# Ind_board.net
KiCad netlist of a schematic drawn in Altium Designer
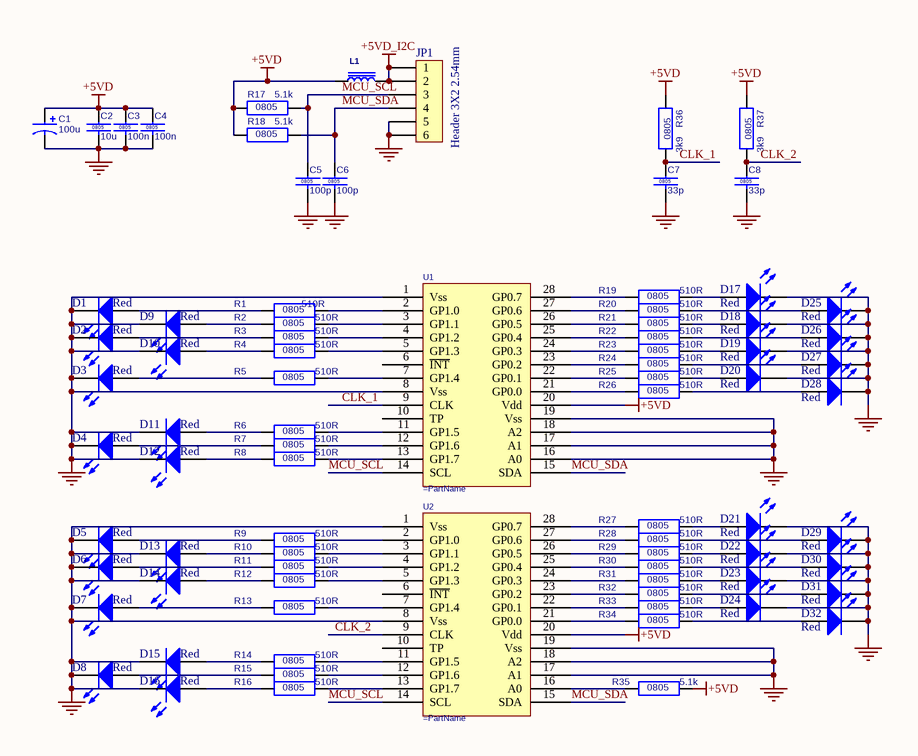
[diagram p0: Ind_board.SchDoc]

(export (version "E")
  (design (tool "Eeschema 10.0.6"))
  (components
    (comp (ref "C1")
      (value "100u")
      (footprint "CEH12.5D10P5.0")
      (description "Electrolytic capacitor")
      (fields
        (field (name "PART NUMBER") "CEH12.5D10P5.0M-50V-100U")
        (field (name "VOLTAGE") "50V")
        (field (name "PUBLISHER") "ppavlov")
      )
      (libsource (lib "Aldiva_Altium_Library") (part "Capacitor_polar"))
    )
    (comp (ref "C2")
      (value "10u")
      (footprint "RC0805")
      (description "Chip capacitor, 20p")
      (fields
        (field (name "VOLTAGE") "16V")
        (field (name "MANUFACTURER") "KEMET, YAGEO")
        (field (name "CASE") "0805")
        (field (name "PUBLISHER") "tkondratyuk")
      )
      (libsource (lib "Aldiva_Altium_Library") (part "Capacitor_nonpolar_case"))
    )
    (comp (ref "C3")
      (value "100n")
      (footprint "RC0805")
      (description "Chip capacitor, 20p")
      (fields
        (field (name "VOLTAGE") "50V")
        (field (name "MANUFACTURER") "KEMET, YAGEO")
        (field (name "CASE") "0805")
        (field (name "PUBLISHER") "ppavlov")
      )
      (libsource (lib "Aldiva_Altium_Library") (part "Capacitor_nonpolar_case"))
    )
    (comp (ref "C4")
      (value "100n")
      (footprint "RC0805")
      (description "Chip capacitor, 20p")
      (fields
        (field (name "VOLTAGE") "50V")
        (field (name "MANUFACTURER") "KEMET, YAGEO")
        (field (name "CASE") "0805")
        (field (name "PUBLISHER") "ppavlov")
      )
      (libsource (lib "Aldiva_Altium_Library") (part "Capacitor_nonpolar_case"))
    )
    (comp (ref "C5")
      (value "100p")
      (footprint "RC0805")
      (description "Chip capacitor, 20p")
      (fields
        (field (name "VOLTAGE") "50V")
        (field (name "MANUFACTURER") "KEMET, YAGEO")
        (field (name "CASE") "0805")
        (field (name "PUBLISHER") "ppavlov")
      )
      (libsource (lib "Aldiva_Altium_Library") (part "Capacitor_nonpolar_case"))
    )
    (comp (ref "C6")
      (value "100p")
      (footprint "RC0805")
      (description "Chip capacitor, 20p")
      (fields
        (field (name "VOLTAGE") "50V")
        (field (name "MANUFACTURER") "KEMET, YAGEO")
        (field (name "CASE") "0805")
        (field (name "PUBLISHER") "ppavlov")
      )
      (libsource (lib "Aldiva_Altium_Library") (part "Capacitor_nonpolar_case"))
    )
    (comp (ref "C7")
      (value "33p")
      (footprint "RC0805")
      (description "Chip capacitor, 20p")
      (fields
        (field (name "VOLTAGE") "50V")
        (field (name "MANUFACTURER") "KEMET, YAGEO")
        (field (name "CASE") "0805")
        (field (name "PUBLISHER") "ppavlov")
      )
      (libsource (lib "Aldiva_Altium_Library") (part "Capacitor_nonpolar_case"))
    )
    (comp (ref "C8")
      (value "33p")
      (footprint "RC0805")
      (description "Chip capacitor, 20p")
      (fields
        (field (name "VOLTAGE") "50V")
        (field (name "MANUFACTURER") "KEMET, YAGEO")
        (field (name "CASE") "0805")
        (field (name "PUBLISHER") "ppavlov")
      )
      (libsource (lib "Aldiva_Altium_Library") (part "Capacitor_nonpolar_case"))
    )
    (comp (ref "D1")
      (value "RED")
      (footprint "LED0805")
      (description "High Performance ChipLED / 0805")
      (fields
        (field (name "COLOR") "Red")
        (field (name "PART NUMBER") "HSMC-C170")
        (field (name "VOLTAGE") "1.9V")
        (field (name "PUBLISHER") "tkondratyuk")
      )
      (libsource (lib "Aldiva_Altium_Library") (part "LED"))
    )
    (comp (ref "D2")
      (value "RED")
      (footprint "LED0805")
      (description "High Performance ChipLED / 0805")
      (fields
        (field (name "COLOR") "Red")
        (field (name "PART NUMBER") "HSMC-C170")
        (field (name "VOLTAGE") "1.9V")
        (field (name "PUBLISHER") "tkondratyuk")
      )
      (libsource (lib "Aldiva_Altium_Library") (part "LED"))
    )
    (comp (ref "D3")
      (value "RED")
      (footprint "LED0805")
      (description "High Performance ChipLED / 0805")
      (fields
        (field (name "COLOR") "Red")
        (field (name "PART NUMBER") "HSMC-C170")
        (field (name "VOLTAGE") "1.9V")
        (field (name "PUBLISHER") "tkondratyuk")
      )
      (libsource (lib "Aldiva_Altium_Library") (part "LED"))
    )
    (comp (ref "D4")
      (value "RED")
      (footprint "LED0805")
      (description "High Performance ChipLED / 0805")
      (fields
        (field (name "COLOR") "Red")
        (field (name "PART NUMBER") "HSMC-C170")
        (field (name "VOLTAGE") "1.9V")
        (field (name "PUBLISHER") "tkondratyuk")
      )
      (libsource (lib "Aldiva_Altium_Library") (part "LED"))
    )
    (comp (ref "D5")
      (value "RED")
      (footprint "LED0805")
      (description "High Performance ChipLED / 0805")
      (fields
        (field (name "COLOR") "Red")
        (field (name "PART NUMBER") "HSMC-C170")
        (field (name "VOLTAGE") "1.9V")
        (field (name "PUBLISHER") "tkondratyuk")
      )
      (libsource (lib "Aldiva_Altium_Library") (part "LED"))
    )
    (comp (ref "D6")
      (value "RED")
      (footprint "LED0805")
      (description "High Performance ChipLED / 0805")
      (fields
        (field (name "COLOR") "Red")
        (field (name "PART NUMBER") "HSMC-C170")
        (field (name "VOLTAGE") "1.9V")
        (field (name "PUBLISHER") "tkondratyuk")
      )
      (libsource (lib "Aldiva_Altium_Library") (part "LED"))
    )
    (comp (ref "D7")
      (value "RED")
      (footprint "LED0805")
      (description "High Performance ChipLED / 0805")
      (fields
        (field (name "COLOR") "Red")
        (field (name "PART NUMBER") "HSMC-C170")
        (field (name "VOLTAGE") "1.9V")
        (field (name "PUBLISHER") "tkondratyuk")
      )
      (libsource (lib "Aldiva_Altium_Library") (part "LED"))
    )
    (comp (ref "D8")
      (value "RED")
      (footprint "LED0805")
      (description "High Performance ChipLED / 0805")
      (fields
        (field (name "COLOR") "Red")
        (field (name "PART NUMBER") "HSMC-C170")
        (field (name "VOLTAGE") "1.9V")
        (field (name "PUBLISHER") "tkondratyuk")
      )
      (libsource (lib "Aldiva_Altium_Library") (part "LED"))
    )
    (comp (ref "D9")
      (value "RED")
      (footprint "LED0805")
      (description "High Performance ChipLED / 0805")
      (fields
        (field (name "COLOR") "Red")
        (field (name "PART NUMBER") "HSMC-C170")
        (field (name "VOLTAGE") "1.9V")
        (field (name "PUBLISHER") "tkondratyuk")
      )
      (libsource (lib "Aldiva_Altium_Library") (part "LED"))
    )
    (comp (ref "D10")
      (value "RED")
      (footprint "LED0805")
      (description "High Performance ChipLED / 0805")
      (fields
        (field (name "COLOR") "Red")
        (field (name "PART NUMBER") "HSMC-C170")
        (field (name "VOLTAGE") "1.9V")
        (field (name "PUBLISHER") "tkondratyuk")
      )
      (libsource (lib "Aldiva_Altium_Library") (part "LED"))
    )
    (comp (ref "D11")
      (value "RED")
      (footprint "LED0805")
      (description "High Performance ChipLED / 0805")
      (fields
        (field (name "COLOR") "Red")
        (field (name "PART NUMBER") "HSMC-C170")
        (field (name "VOLTAGE") "1.9V")
        (field (name "PUBLISHER") "tkondratyuk")
      )
      (libsource (lib "Aldiva_Altium_Library") (part "LED"))
    )
    (comp (ref "D12")
      (value "RED")
      (footprint "LED0805")
      (description "High Performance ChipLED / 0805")
      (fields
        (field (name "COLOR") "Red")
        (field (name "PART NUMBER") "HSMC-C170")
        (field (name "VOLTAGE") "1.9V")
        (field (name "PUBLISHER") "tkondratyuk")
      )
      (libsource (lib "Aldiva_Altium_Library") (part "LED"))
    )
    (comp (ref "D13")
      (value "RED")
      (footprint "LED0805")
      (description "High Performance ChipLED / 0805")
      (fields
        (field (name "COLOR") "Red")
        (field (name "PART NUMBER") "HSMC-C170")
        (field (name "VOLTAGE") "1.9V")
        (field (name "PUBLISHER") "tkondratyuk")
      )
      (libsource (lib "Aldiva_Altium_Library") (part "LED"))
    )
    (comp (ref "D14")
      (value "RED")
      (footprint "LED0805")
      (description "High Performance ChipLED / 0805")
      (fields
        (field (name "COLOR") "Red")
        (field (name "PART NUMBER") "HSMC-C170")
        (field (name "VOLTAGE") "1.9V")
        (field (name "PUBLISHER") "tkondratyuk")
      )
      (libsource (lib "Aldiva_Altium_Library") (part "LED"))
    )
    (comp (ref "D15")
      (value "RED")
      (footprint "LED0805")
      (description "High Performance ChipLED / 0805")
      (fields
        (field (name "COLOR") "Red")
        (field (name "PART NUMBER") "HSMC-C170")
        (field (name "VOLTAGE") "1.9V")
        (field (name "PUBLISHER") "tkondratyuk")
      )
      (libsource (lib "Aldiva_Altium_Library") (part "LED"))
    )
    (comp (ref "D16")
      (value "RED")
      (footprint "LED0805")
      (description "High Performance ChipLED / 0805")
      (fields
        (field (name "COLOR") "Red")
        (field (name "PART NUMBER") "HSMC-C170")
        (field (name "VOLTAGE") "1.9V")
        (field (name "PUBLISHER") "tkondratyuk")
      )
      (libsource (lib "Aldiva_Altium_Library") (part "LED"))
    )
    (comp (ref "D17")
      (value "RED")
      (footprint "LED0805")
      (description "High Performance ChipLED / 0805")
      (fields
        (field (name "COLOR") "Red")
        (field (name "PART NUMBER") "HSMC-C170")
        (field (name "VOLTAGE") "1.9V")
        (field (name "PUBLISHER") "tkondratyuk")
      )
      (libsource (lib "Aldiva_Altium_Library") (part "LED"))
    )
    (comp (ref "D18")
      (value "RED")
      (footprint "LED0805")
      (description "High Performance ChipLED / 0805")
      (fields
        (field (name "COLOR") "Red")
        (field (name "PART NUMBER") "HSMC-C170")
        (field (name "VOLTAGE") "1.9V")
        (field (name "PUBLISHER") "tkondratyuk")
      )
      (libsource (lib "Aldiva_Altium_Library") (part "LED"))
    )
    (comp (ref "D19")
      (value "RED")
      (footprint "LED0805")
      (description "High Performance ChipLED / 0805")
      (fields
        (field (name "COLOR") "Red")
        (field (name "PART NUMBER") "HSMC-C170")
        (field (name "VOLTAGE") "1.9V")
        (field (name "PUBLISHER") "tkondratyuk")
      )
      (libsource (lib "Aldiva_Altium_Library") (part "LED"))
    )
    (comp (ref "D20")
      (value "RED")
      (footprint "LED0805")
      (description "High Performance ChipLED / 0805")
      (fields
        (field (name "COLOR") "Red")
        (field (name "PART NUMBER") "HSMC-C170")
        (field (name "VOLTAGE") "1.9V")
        (field (name "PUBLISHER") "tkondratyuk")
      )
      (libsource (lib "Aldiva_Altium_Library") (part "LED"))
    )
    (comp (ref "D21")
      (value "RED")
      (footprint "LED0805")
      (description "High Performance ChipLED / 0805")
      (fields
        (field (name "COLOR") "Red")
        (field (name "PART NUMBER") "HSMC-C170")
        (field (name "VOLTAGE") "1.9V")
        (field (name "PUBLISHER") "tkondratyuk")
      )
      (libsource (lib "Aldiva_Altium_Library") (part "LED"))
    )
    (comp (ref "D22")
      (value "RED")
      (footprint "LED0805")
      (description "High Performance ChipLED / 0805")
      (fields
        (field (name "COLOR") "Red")
        (field (name "PART NUMBER") "HSMC-C170")
        (field (name "VOLTAGE") "1.9V")
        (field (name "PUBLISHER") "tkondratyuk")
      )
      (libsource (lib "Aldiva_Altium_Library") (part "LED"))
    )
    (comp (ref "D23")
      (value "RED")
      (footprint "LED0805")
      (description "High Performance ChipLED / 0805")
      (fields
        (field (name "COLOR") "Red")
        (field (name "PART NUMBER") "HSMC-C170")
        (field (name "VOLTAGE") "1.9V")
        (field (name "PUBLISHER") "tkondratyuk")
      )
      (libsource (lib "Aldiva_Altium_Library") (part "LED"))
    )
    (comp (ref "D24")
      (value "RED")
      (footprint "LED0805")
      (description "High Performance ChipLED / 0805")
      (fields
        (field (name "COLOR") "Red")
        (field (name "PART NUMBER") "HSMC-C170")
        (field (name "VOLTAGE") "1.9V")
        (field (name "PUBLISHER") "tkondratyuk")
      )
      (libsource (lib "Aldiva_Altium_Library") (part "LED"))
    )
    (comp (ref "D25")
      (value "RED")
      (footprint "LED0805")
      (description "High Performance ChipLED / 0805")
      (fields
        (field (name "COLOR") "Red")
        (field (name "PART NUMBER") "HSMC-C170")
        (field (name "VOLTAGE") "1.9V")
        (field (name "PUBLISHER") "tkondratyuk")
      )
      (libsource (lib "Aldiva_Altium_Library") (part "LED"))
    )
    (comp (ref "D26")
      (value "RED")
      (footprint "LED0805")
      (description "High Performance ChipLED / 0805")
      (fields
        (field (name "COLOR") "Red")
        (field (name "PART NUMBER") "HSMC-C170")
        (field (name "VOLTAGE") "1.9V")
        (field (name "PUBLISHER") "tkondratyuk")
      )
      (libsource (lib "Aldiva_Altium_Library") (part "LED"))
    )
    (comp (ref "D27")
      (value "RED")
      (footprint "LED0805")
      (description "High Performance ChipLED / 0805")
      (fields
        (field (name "COLOR") "Red")
        (field (name "PART NUMBER") "HSMC-C170")
        (field (name "VOLTAGE") "1.9V")
        (field (name "PUBLISHER") "tkondratyuk")
      )
      (libsource (lib "Aldiva_Altium_Library") (part "LED"))
    )
    (comp (ref "D28")
      (value "RED")
      (footprint "LED0805")
      (description "High Performance ChipLED / 0805")
      (fields
        (field (name "COLOR") "Red")
        (field (name "PART NUMBER") "HSMC-C170")
        (field (name "VOLTAGE") "1.9V")
        (field (name "PUBLISHER") "tkondratyuk")
      )
      (libsource (lib "Aldiva_Altium_Library") (part "LED"))
    )
    (comp (ref "D29")
      (value "RED")
      (footprint "LED0805")
      (description "High Performance ChipLED / 0805")
      (fields
        (field (name "COLOR") "Red")
        (field (name "PART NUMBER") "HSMC-C170")
        (field (name "VOLTAGE") "1.9V")
        (field (name "PUBLISHER") "tkondratyuk")
      )
      (libsource (lib "Aldiva_Altium_Library") (part "LED"))
    )
    (comp (ref "D30")
      (value "RED")
      (footprint "LED0805")
      (description "High Performance ChipLED / 0805")
      (fields
        (field (name "COLOR") "Red")
        (field (name "PART NUMBER") "HSMC-C170")
        (field (name "VOLTAGE") "1.9V")
        (field (name "PUBLISHER") "tkondratyuk")
      )
      (libsource (lib "Aldiva_Altium_Library") (part "LED"))
    )
    (comp (ref "D31")
      (value "RED")
      (footprint "LED0805")
      (description "High Performance ChipLED / 0805")
      (fields
        (field (name "COLOR") "Red")
        (field (name "PART NUMBER") "HSMC-C170")
        (field (name "VOLTAGE") "1.9V")
        (field (name "PUBLISHER") "tkondratyuk")
      )
      (libsource (lib "Aldiva_Altium_Library") (part "LED"))
    )
    (comp (ref "D32")
      (value "RED")
      (footprint "LED0805")
      (description "High Performance ChipLED / 0805")
      (fields
        (field (name "COLOR") "Red")
        (field (name "PART NUMBER") "HSMC-C170")
        (field (name "VOLTAGE") "1.9V")
        (field (name "PUBLISHER") "tkondratyuk")
      )
      (libsource (lib "Aldiva_Altium_Library") (part "LED"))
    )
    (comp (ref "JP1")
      (value "Header 3X2 2.54mm")
      (footprint "Pins2x3_2.54mm")
      (fields (field (name "PUBLISHER") "ppavlov"))
      (libsource (lib "Aldiva_Altium_Library") (part "Header 3X2 2.54mm"))
    )
    (comp (ref "L1")
      (value "BLM31PG601SN1")
      (footprint "RC1206")
      (description "Ferrite bead smd")
      (fields
        (field (name "MANUFACTURER") "Murata")
        (field (name "TOLERANCE") "25%")
        (field (name "AUTHOR") "PPavlov")
        (field (name "PUBLISHER") "ppavlov")
      )
      (libsource (lib "Aldiva_Altium_Library") (part "BLM31PG601SN1"))
    )
    (comp (ref "R1")
      (value "510R")
      (footprint "RC0805")
      (description "Chip resistor")
      (fields
        (field (name "CASE") "0805")
        (field (name "PART NUMBER") "RC0805F-510R")
        (field (name "VOLTAGE") "200V")
        (field (name "PUBLISHER") "ppavlov")
      )
      (libsource (lib "Aldiva_Altium_Library") (part "Resistor"))
    )
    (comp (ref "R2")
      (value "510R")
      (footprint "RC0805")
      (description "Chip resistor")
      (fields
        (field (name "CASE") "0805")
        (field (name "PART NUMBER") "RC0805F-510R")
        (field (name "VOLTAGE") "200V")
        (field (name "PUBLISHER") "ppavlov")
      )
      (libsource (lib "Aldiva_Altium_Library") (part "Resistor"))
    )
    (comp (ref "R3")
      (value "510R")
      (footprint "RC0805")
      (description "Chip resistor")
      (fields
        (field (name "CASE") "0805")
        (field (name "PART NUMBER") "RC0805F-510R")
        (field (name "VOLTAGE") "200V")
        (field (name "PUBLISHER") "ppavlov")
      )
      (libsource (lib "Aldiva_Altium_Library") (part "Resistor"))
    )
    (comp (ref "R4")
      (value "510R")
      (footprint "RC0805")
      (description "Chip resistor")
      (fields
        (field (name "CASE") "0805")
        (field (name "PART NUMBER") "RC0805F-510R")
        (field (name "VOLTAGE") "200V")
        (field (name "PUBLISHER") "ppavlov")
      )
      (libsource (lib "Aldiva_Altium_Library") (part "Resistor"))
    )
    (comp (ref "R5")
      (value "510R")
      (footprint "RC0805")
      (description "Chip resistor")
      (fields
        (field (name "CASE") "0805")
        (field (name "PART NUMBER") "RC0805F-510R")
        (field (name "VOLTAGE") "200V")
        (field (name "PUBLISHER") "ppavlov")
      )
      (libsource (lib "Aldiva_Altium_Library") (part "Resistor"))
    )
    (comp (ref "R6")
      (value "510R")
      (footprint "RC0805")
      (description "Chip resistor")
      (fields
        (field (name "CASE") "0805")
        (field (name "PART NUMBER") "RC0805F-510R")
        (field (name "VOLTAGE") "200V")
        (field (name "PUBLISHER") "ppavlov")
      )
      (libsource (lib "Aldiva_Altium_Library") (part "Resistor"))
    )
    (comp (ref "R7")
      (value "510R")
      (footprint "RC0805")
      (description "Chip resistor")
      (fields
        (field (name "CASE") "0805")
        (field (name "PART NUMBER") "RC0805F-510R")
        (field (name "VOLTAGE") "200V")
        (field (name "PUBLISHER") "ppavlov")
      )
      (libsource (lib "Aldiva_Altium_Library") (part "Resistor"))
    )
    (comp (ref "R8")
      (value "510R")
      (footprint "RC0805")
      (description "Chip resistor")
      (fields
        (field (name "CASE") "0805")
        (field (name "PART NUMBER") "RC0805F-510R")
        (field (name "VOLTAGE") "200V")
        (field (name "PUBLISHER") "ppavlov")
      )
      (libsource (lib "Aldiva_Altium_Library") (part "Resistor"))
    )
    (comp (ref "R9")
      (value "510R")
      (footprint "RC0805")
      (description "Chip resistor")
      (fields
        (field (name "CASE") "0805")
        (field (name "PART NUMBER") "RC0805F-510R")
        (field (name "VOLTAGE") "200V")
        (field (name "PUBLISHER") "ppavlov")
      )
      (libsource (lib "Aldiva_Altium_Library") (part "Resistor"))
    )
    (comp (ref "R10")
      (value "510R")
      (footprint "RC0805")
      (description "Chip resistor")
      (fields
        (field (name "CASE") "0805")
        (field (name "PART NUMBER") "RC0805F-510R")
        (field (name "VOLTAGE") "200V")
        (field (name "PUBLISHER") "ppavlov")
      )
      (libsource (lib "Aldiva_Altium_Library") (part "Resistor"))
    )
    (comp (ref "R11")
      (value "510R")
      (footprint "RC0805")
      (description "Chip resistor")
      (fields
        (field (name "CASE") "0805")
        (field (name "PART NUMBER") "RC0805F-510R")
        (field (name "VOLTAGE") "200V")
        (field (name "PUBLISHER") "ppavlov")
      )
      (libsource (lib "Aldiva_Altium_Library") (part "Resistor"))
    )
    (comp (ref "R12")
      (value "510R")
      (footprint "RC0805")
      (description "Chip resistor")
      (fields
        (field (name "CASE") "0805")
        (field (name "PART NUMBER") "RC0805F-510R")
        (field (name "VOLTAGE") "200V")
        (field (name "PUBLISHER") "ppavlov")
      )
      (libsource (lib "Aldiva_Altium_Library") (part "Resistor"))
    )
    (comp (ref "R13")
      (value "510R")
      (footprint "RC0805")
      (description "Chip resistor")
      (fields
        (field (name "CASE") "0805")
        (field (name "PART NUMBER") "RC0805F-510R")
        (field (name "VOLTAGE") "200V")
        (field (name "PUBLISHER") "ppavlov")
      )
      (libsource (lib "Aldiva_Altium_Library") (part "Resistor"))
    )
    (comp (ref "R14")
      (value "510R")
      (footprint "RC0805")
      (description "Chip resistor")
      (fields
        (field (name "CASE") "0805")
        (field (name "PART NUMBER") "RC0805F-510R")
        (field (name "VOLTAGE") "200V")
        (field (name "PUBLISHER") "ppavlov")
      )
      (libsource (lib "Aldiva_Altium_Library") (part "Resistor"))
    )
    (comp (ref "R15")
      (value "510R")
      (footprint "RC0805")
      (description "Chip resistor")
      (fields
        (field (name "CASE") "0805")
        (field (name "PART NUMBER") "RC0805F-510R")
        (field (name "VOLTAGE") "200V")
        (field (name "PUBLISHER") "ppavlov")
      )
      (libsource (lib "Aldiva_Altium_Library") (part "Resistor"))
    )
    (comp (ref "R16")
      (value "510R")
      (footprint "RC0805")
      (description "Chip resistor")
      (fields
        (field (name "CASE") "0805")
        (field (name "PART NUMBER") "RC0805F-510R")
        (field (name "VOLTAGE") "200V")
        (field (name "PUBLISHER") "ppavlov")
      )
      (libsource (lib "Aldiva_Altium_Library") (part "Resistor"))
    )
    (comp (ref "R17")
      (value "5.1k")
      (footprint "RC0805")
      (description "Chip resistor")
      (fields
        (field (name "CASE") "0805")
        (field (name "PART NUMBER") "RC0805F-5K10")
        (field (name "VOLTAGE") "200V")
        (field (name "PUBLISHER") "ppavlov")
      )
      (libsource (lib "Aldiva_Altium_Library") (part "Resistor"))
    )
    (comp (ref "R18")
      (value "5.1k")
      (footprint "RC0805")
      (description "Chip resistor")
      (fields
        (field (name "CASE") "0805")
        (field (name "PART NUMBER") "RC0805F-5K10")
        (field (name "VOLTAGE") "200V")
        (field (name "PUBLISHER") "ppavlov")
      )
      (libsource (lib "Aldiva_Altium_Library") (part "Resistor"))
    )
    (comp (ref "R19")
      (value "510R")
      (footprint "RC0805")
      (description "Chip resistor")
      (fields
        (field (name "CASE") "0805")
        (field (name "PART NUMBER") "RC0805F-510R")
        (field (name "VOLTAGE") "200V")
        (field (name "PUBLISHER") "ppavlov")
      )
      (libsource (lib "Aldiva_Altium_Library") (part "Resistor"))
    )
    (comp (ref "R20")
      (value "510R")
      (footprint "RC0805")
      (description "Chip resistor")
      (fields
        (field (name "CASE") "0805")
        (field (name "PART NUMBER") "RC0805F-510R")
        (field (name "VOLTAGE") "200V")
        (field (name "PUBLISHER") "ppavlov")
      )
      (libsource (lib "Aldiva_Altium_Library") (part "Resistor"))
    )
    (comp (ref "R21")
      (value "510R")
      (footprint "RC0805")
      (description "Chip resistor")
      (fields
        (field (name "CASE") "0805")
        (field (name "PART NUMBER") "RC0805F-510R")
        (field (name "VOLTAGE") "200V")
        (field (name "PUBLISHER") "ppavlov")
      )
      (libsource (lib "Aldiva_Altium_Library") (part "Resistor"))
    )
    (comp (ref "R22")
      (value "510R")
      (footprint "RC0805")
      (description "Chip resistor")
      (fields
        (field (name "CASE") "0805")
        (field (name "PART NUMBER") "RC0805F-510R")
        (field (name "VOLTAGE") "200V")
        (field (name "PUBLISHER") "ppavlov")
      )
      (libsource (lib "Aldiva_Altium_Library") (part "Resistor"))
    )
    (comp (ref "R23")
      (value "510R")
      (footprint "RC0805")
      (description "Chip resistor")
      (fields
        (field (name "CASE") "0805")
        (field (name "PART NUMBER") "RC0805F-510R")
        (field (name "VOLTAGE") "200V")
        (field (name "PUBLISHER") "ppavlov")
      )
      (libsource (lib "Aldiva_Altium_Library") (part "Resistor"))
    )
    (comp (ref "R24")
      (value "510R")
      (footprint "RC0805")
      (description "Chip resistor")
      (fields
        (field (name "CASE") "0805")
        (field (name "PART NUMBER") "RC0805F-510R")
        (field (name "VOLTAGE") "200V")
        (field (name "PUBLISHER") "ppavlov")
      )
      (libsource (lib "Aldiva_Altium_Library") (part "Resistor"))
    )
    (comp (ref "R25")
      (value "510R")
      (footprint "RC0805")
      (description "Chip resistor")
      (fields
        (field (name "CASE") "0805")
        (field (name "PART NUMBER") "RC0805F-510R")
        (field (name "VOLTAGE") "200V")
        (field (name "PUBLISHER") "ppavlov")
      )
      (libsource (lib "Aldiva_Altium_Library") (part "Resistor"))
    )
    (comp (ref "R26")
      (value "510R")
      (footprint "RC0805")
      (description "Chip resistor")
      (fields
        (field (name "CASE") "0805")
        (field (name "PART NUMBER") "RC0805F-510R")
        (field (name "VOLTAGE") "200V")
        (field (name "PUBLISHER") "ppavlov")
      )
      (libsource (lib "Aldiva_Altium_Library") (part "Resistor"))
    )
    (comp (ref "R27")
      (value "510R")
      (footprint "RC0805")
      (description "Chip resistor")
      (fields
        (field (name "CASE") "0805")
        (field (name "PART NUMBER") "RC0805F-510R")
        (field (name "VOLTAGE") "200V")
        (field (name "PUBLISHER") "ppavlov")
      )
      (libsource (lib "Aldiva_Altium_Library") (part "Resistor"))
    )
    (comp (ref "R28")
      (value "510R")
      (footprint "RC0805")
      (description "Chip resistor")
      (fields
        (field (name "CASE") "0805")
        (field (name "PART NUMBER") "RC0805F-510R")
        (field (name "VOLTAGE") "200V")
        (field (name "PUBLISHER") "ppavlov")
      )
      (libsource (lib "Aldiva_Altium_Library") (part "Resistor"))
    )
    (comp (ref "R29")
      (value "510R")
      (footprint "RC0805")
      (description "Chip resistor")
      (fields
        (field (name "CASE") "0805")
        (field (name "PART NUMBER") "RC0805F-510R")
        (field (name "VOLTAGE") "200V")
        (field (name "PUBLISHER") "ppavlov")
      )
      (libsource (lib "Aldiva_Altium_Library") (part "Resistor"))
    )
    (comp (ref "R30")
      (value "510R")
      (footprint "RC0805")
      (description "Chip resistor")
      (fields
        (field (name "CASE") "0805")
        (field (name "PART NUMBER") "RC0805F-510R")
        (field (name "VOLTAGE") "200V")
        (field (name "PUBLISHER") "ppavlov")
      )
      (libsource (lib "Aldiva_Altium_Library") (part "Resistor"))
    )
    (comp (ref "R31")
      (value "510R")
      (footprint "RC0805")
      (description "Chip resistor")
      (fields
        (field (name "CASE") "0805")
        (field (name "PART NUMBER") "RC0805F-510R")
        (field (name "VOLTAGE") "200V")
        (field (name "PUBLISHER") "ppavlov")
      )
      (libsource (lib "Aldiva_Altium_Library") (part "Resistor"))
    )
    (comp (ref "R32")
      (value "510R")
      (footprint "RC0805")
      (description "Chip resistor")
      (fields
        (field (name "CASE") "0805")
        (field (name "PART NUMBER") "RC0805F-510R")
        (field (name "VOLTAGE") "200V")
        (field (name "PUBLISHER") "ppavlov")
      )
      (libsource (lib "Aldiva_Altium_Library") (part "Resistor"))
    )
    (comp (ref "R33")
      (value "510R")
      (footprint "RC0805")
      (description "Chip resistor")
      (fields
        (field (name "CASE") "0805")
        (field (name "PART NUMBER") "RC0805F-510R")
        (field (name "VOLTAGE") "200V")
        (field (name "PUBLISHER") "ppavlov")
      )
      (libsource (lib "Aldiva_Altium_Library") (part "Resistor"))
    )
    (comp (ref "R34")
      (value "510R")
      (footprint "RC0805")
      (description "Chip resistor")
      (fields
        (field (name "CASE") "0805")
        (field (name "PART NUMBER") "RC0805F-510R")
        (field (name "VOLTAGE") "200V")
        (field (name "PUBLISHER") "ppavlov")
      )
      (libsource (lib "Aldiva_Altium_Library") (part "Resistor"))
    )
    (comp (ref "R35")
      (value "5.1k")
      (footprint "RC0805")
      (description "Chip resistor")
      (fields
        (field (name "CASE") "0805")
        (field (name "PART NUMBER") "RC0805F-5K10")
        (field (name "VOLTAGE") "200V")
        (field (name "PUBLISHER") "ppavlov")
      )
      (libsource (lib "Aldiva_Altium_Library") (part "Resistor"))
    )
    (comp (ref "R36")
      (value "3k9")
      (footprint "RC0805")
      (description "Chip resistor")
      (fields
        (field (name "CASE") "0805")
        (field (name "PART NUMBER") "RC0805F-3K90")
        (field (name "VOLTAGE") "200V")
        (field (name "PUBLISHER") "ppavlov")
      )
      (libsource (lib "Aldiva_Altium_Library") (part "Resistor"))
    )
    (comp (ref "R37")
      (value "3k9")
      (footprint "RC0805")
      (description "Chip resistor")
      (fields
        (field (name "CASE") "0805")
        (field (name "PART NUMBER") "RC0805F-3K90")
        (field (name "VOLTAGE") "200V")
        (field (name "PUBLISHER") "ppavlov")
      )
      (libsource (lib "Aldiva_Altium_Library") (part "Resistor"))
    )
    (comp (ref "U1")
      (value "~")
      (footprint "SO-28")
      (description "16-Bit I2C™ I/O Expander")
      (fields
        (field (name "PART NUMBER") "MCP23016-I/SO")
        (field (name "MANUFACTURER") "Microchip")
        (field (name "PUBLISHER") "ppavlov")
      )
      (libsource (lib "Aldiva_Altium_Library") (part "MCP23016"))
    )
    (comp (ref "U2")
      (value "~")
      (footprint "SO-28")
      (description "16-Bit I2C™ I/O Expander")
      (fields
        (field (name "PART NUMBER") "MCP23016-I/SO")
        (field (name "MANUFACTURER") "Microchip")
        (field (name "PUBLISHER") "ppavlov")
      )
      (libsource (lib "Aldiva_Altium_Library") (part "MCP23016"))
    )
  )
  (nets
    (net (code "1") (name "+5VD") (class "Default")
      (node (ref "C1") (pin "1") (pinfunction "1_1") (pintype "passive"))
      (node (ref "C2") (pin "1") (pinfunction "1_1") (pintype "passive"))
      (node (ref "C3") (pin "1") (pinfunction "1_1") (pintype "passive"))
      (node (ref "C4") (pin "1") (pinfunction "1_1") (pintype "passive"))
      (node (ref "L1") (pin "1") (pinfunction "1_1") (pintype "passive"))
      (node (ref "R17") (pin "1") (pinfunction "1_1") (pintype "passive"))
      (node (ref "R18") (pin "1") (pinfunction "1_1") (pintype "passive"))
      (node (ref "R35") (pin "2") (pinfunction "2_2") (pintype "passive"))
      (node (ref "R36") (pin "1") (pinfunction "1_1") (pintype "passive"))
      (node (ref "R37") (pin "1") (pinfunction "1_1") (pintype "passive"))
      (node (ref "U1") (pin "20") (pinfunction "Vdd_20") (pintype "passive"))
      (node (ref "U2") (pin "20") (pinfunction "Vdd_20") (pintype "passive"))
    )
    (net (code "2") (name "+5VD_I2C") (class "Default")
      (node (ref "JP1") (pin "1") (pinfunction "1_1") (pintype "passive"))
      (node (ref "JP1") (pin "2") (pinfunction "2_2") (pintype "passive"))
      (node (ref "L1") (pin "2") (pinfunction "2_2") (pintype "passive"))
    )
    (net (code "3") (name "/CLK_1") (class "Default")
      (node (ref "C7") (pin "1") (pinfunction "1_1") (pintype "passive"))
      (node (ref "R36") (pin "2") (pinfunction "2_2") (pintype "passive"))
      (node (ref "U1") (pin "9") (pinfunction "CLK_9") (pintype "passive"))
    )
    (net (code "4") (name "/CLK_2") (class "Default")
      (node (ref "C8") (pin "1") (pinfunction "1_1") (pintype "passive"))
      (node (ref "R37") (pin "2") (pinfunction "2_2") (pintype "passive"))
      (node (ref "U2") (pin "9") (pinfunction "CLK_9") (pintype "passive"))
    )
    (net (code "5") (name "/MCU_SCL") (class "Default")
      (node (ref "C5") (pin "1") (pinfunction "1_1") (pintype "passive"))
      (node (ref "JP1") (pin "3") (pinfunction "3_3") (pintype "passive"))
      (node (ref "R17") (pin "2") (pinfunction "2_2") (pintype "passive"))
      (node (ref "U1") (pin "14") (pinfunction "SCL_14") (pintype "passive"))
      (node (ref "U2") (pin "14") (pinfunction "SCL_14") (pintype "passive"))
    )
    (net (code "6") (name "/MCU_SDA") (class "Default")
      (node (ref "C6") (pin "1") (pinfunction "1_1") (pintype "passive"))
      (node (ref "JP1") (pin "4") (pinfunction "4_4") (pintype "passive"))
      (node (ref "R18") (pin "2") (pinfunction "2_2") (pintype "passive"))
      (node (ref "U1") (pin "15") (pinfunction "SDA_15") (pintype "passive"))
      (node (ref "U2") (pin "15") (pinfunction "SDA_15") (pintype "passive"))
    )
    (net (code "7") (name "DGND") (class "Default")
      (node (ref "C1") (pin "2") (pinfunction "2_2") (pintype "passive"))
      (node (ref "C2") (pin "2") (pinfunction "2_2") (pintype "passive"))
      (node (ref "C3") (pin "2") (pinfunction "2_2") (pintype "passive"))
      (node (ref "C4") (pin "2") (pinfunction "2_2") (pintype "passive"))
      (node (ref "C5") (pin "2") (pinfunction "2_2") (pintype "passive"))
      (node (ref "C6") (pin "2") (pinfunction "2_2") (pintype "passive"))
      (node (ref "C7") (pin "2") (pinfunction "2_2") (pintype "passive"))
      (node (ref "C8") (pin "2") (pinfunction "2_2") (pintype "passive"))
      (node (ref "D1") (pin "1") (pinfunction "K_1") (pintype "passive"))
      (node (ref "D10") (pin "1") (pinfunction "K_1") (pintype "passive"))
      (node (ref "D11") (pin "1") (pinfunction "K_1") (pintype "passive"))
      (node (ref "D12") (pin "1") (pinfunction "K_1") (pintype "passive"))
      (node (ref "D13") (pin "1") (pinfunction "K_1") (pintype "passive"))
      (node (ref "D14") (pin "1") (pinfunction "K_1") (pintype "passive"))
      (node (ref "D15") (pin "1") (pinfunction "K_1") (pintype "passive"))
      (node (ref "D16") (pin "1") (pinfunction "K_1") (pintype "passive"))
      (node (ref "D17") (pin "1") (pinfunction "K_1") (pintype "passive"))
      (node (ref "D18") (pin "1") (pinfunction "K_1") (pintype "passive"))
      (node (ref "D19") (pin "1") (pinfunction "K_1") (pintype "passive"))
      (node (ref "D2") (pin "1") (pinfunction "K_1") (pintype "passive"))
      (node (ref "D20") (pin "1") (pinfunction "K_1") (pintype "passive"))
      (node (ref "D21") (pin "1") (pinfunction "K_1") (pintype "passive"))
      (node (ref "D22") (pin "1") (pinfunction "K_1") (pintype "passive"))
      (node (ref "D23") (pin "1") (pinfunction "K_1") (pintype "passive"))
      (node (ref "D24") (pin "1") (pinfunction "K_1") (pintype "passive"))
      (node (ref "D25") (pin "1") (pinfunction "K_1") (pintype "passive"))
      (node (ref "D26") (pin "1") (pinfunction "K_1") (pintype "passive"))
      (node (ref "D27") (pin "1") (pinfunction "K_1") (pintype "passive"))
      (node (ref "D28") (pin "1") (pinfunction "K_1") (pintype "passive"))
      (node (ref "D29") (pin "1") (pinfunction "K_1") (pintype "passive"))
      (node (ref "D3") (pin "1") (pinfunction "K_1") (pintype "passive"))
      (node (ref "D30") (pin "1") (pinfunction "K_1") (pintype "passive"))
      (node (ref "D31") (pin "1") (pinfunction "K_1") (pintype "passive"))
      (node (ref "D32") (pin "1") (pinfunction "K_1") (pintype "passive"))
      (node (ref "D4") (pin "1") (pinfunction "K_1") (pintype "passive"))
      (node (ref "D5") (pin "1") (pinfunction "K_1") (pintype "passive"))
      (node (ref "D6") (pin "1") (pinfunction "K_1") (pintype "passive"))
      (node (ref "D7") (pin "1") (pinfunction "K_1") (pintype "passive"))
      (node (ref "D8") (pin "1") (pinfunction "K_1") (pintype "passive"))
      (node (ref "D9") (pin "1") (pinfunction "K_1") (pintype "passive"))
      (node (ref "JP1") (pin "5") (pinfunction "5_5") (pintype "passive"))
      (node (ref "JP1") (pin "6") (pinfunction "6_6") (pintype "passive"))
      (node (ref "U1") (pin "1") (pinfunction "Vss_1") (pintype "passive"))
      (node (ref "U1") (pin "16") (pinfunction "A0_16") (pintype "passive"))
      (node (ref "U1") (pin "17") (pinfunction "A1_17") (pintype "passive"))
      (node (ref "U1") (pin "18") (pinfunction "A2_18") (pintype "passive"))
      (node (ref "U1") (pin "19") (pinfunction "Vss_19") (pintype "passive"))
      (node (ref "U1") (pin "8") (pinfunction "Vss_8") (pintype "passive"))
      (node (ref "U2") (pin "1") (pinfunction "Vss_1") (pintype "passive"))
      (node (ref "U2") (pin "17") (pinfunction "A1_17") (pintype "passive"))
      (node (ref "U2") (pin "18") (pinfunction "A2_18") (pintype "passive"))
      (node (ref "U2") (pin "19") (pinfunction "Vss_19") (pintype "passive"))
      (node (ref "U2") (pin "8") (pinfunction "Vss_8") (pintype "passive"))
    )
    (net (code "8") (name "Net-(D1-A)") (class "Default")
      (node (ref "D1") (pin "2") (pinfunction "A_2") (pintype "passive"))
      (node (ref "R1") (pin "1") (pinfunction "1_1") (pintype "passive"))
    )
    (net (code "9") (name "Net-(D2-A)") (class "Default")
      (node (ref "D2") (pin "2") (pinfunction "A_2") (pintype "passive"))
      (node (ref "R3") (pin "1") (pinfunction "1_1") (pintype "passive"))
    )
    (net (code "10") (name "Net-(D3-A)") (class "Default")
      (node (ref "D3") (pin "2") (pinfunction "A_2") (pintype "passive"))
      (node (ref "R5") (pin "1") (pinfunction "1_1") (pintype "passive"))
    )
    (net (code "11") (name "Net-(D4-A)") (class "Default")
      (node (ref "D4") (pin "2") (pinfunction "A_2") (pintype "passive"))
      (node (ref "R7") (pin "1") (pinfunction "1_1") (pintype "passive"))
    )
    (net (code "12") (name "Net-(D5-A)") (class "Default")
      (node (ref "D5") (pin "2") (pinfunction "A_2") (pintype "passive"))
      (node (ref "R9") (pin "1") (pinfunction "1_1") (pintype "passive"))
    )
    (net (code "13") (name "Net-(D6-A)") (class "Default")
      (node (ref "D6") (pin "2") (pinfunction "A_2") (pintype "passive"))
      (node (ref "R11") (pin "1") (pinfunction "1_1") (pintype "passive"))
    )
    (net (code "14") (name "Net-(D7-A)") (class "Default")
      (node (ref "D7") (pin "2") (pinfunction "A_2") (pintype "passive"))
      (node (ref "R13") (pin "1") (pinfunction "1_1") (pintype "passive"))
    )
    (net (code "15") (name "Net-(D8-A)") (class "Default")
      (node (ref "D8") (pin "2") (pinfunction "A_2") (pintype "passive"))
      (node (ref "R15") (pin "1") (pinfunction "1_1") (pintype "passive"))
    )
    (net (code "16") (name "Net-(D9-A)") (class "Default")
      (node (ref "D9") (pin "2") (pinfunction "A_2") (pintype "passive"))
      (node (ref "R2") (pin "1") (pinfunction "1_1") (pintype "passive"))
    )
    (net (code "17") (name "Net-(D10-A)") (class "Default")
      (node (ref "D10") (pin "2") (pinfunction "A_2") (pintype "passive"))
      (node (ref "R4") (pin "1") (pinfunction "1_1") (pintype "passive"))
    )
    (net (code "18") (name "Net-(D11-A)") (class "Default")
      (node (ref "D11") (pin "2") (pinfunction "A_2") (pintype "passive"))
      (node (ref "R6") (pin "1") (pinfunction "1_1") (pintype "passive"))
    )
    (net (code "19") (name "Net-(D12-A)") (class "Default")
      (node (ref "D12") (pin "2") (pinfunction "A_2") (pintype "passive"))
      (node (ref "R8") (pin "1") (pinfunction "1_1") (pintype "passive"))
    )
    (net (code "20") (name "Net-(D13-A)") (class "Default")
      (node (ref "D13") (pin "2") (pinfunction "A_2") (pintype "passive"))
      (node (ref "R10") (pin "1") (pinfunction "1_1") (pintype "passive"))
    )
    (net (code "21") (name "Net-(D14-A)") (class "Default")
      (node (ref "D14") (pin "2") (pinfunction "A_2") (pintype "passive"))
      (node (ref "R12") (pin "1") (pinfunction "1_1") (pintype "passive"))
    )
    (net (code "22") (name "Net-(D15-A)") (class "Default")
      (node (ref "D15") (pin "2") (pinfunction "A_2") (pintype "passive"))
      (node (ref "R14") (pin "1") (pinfunction "1_1") (pintype "passive"))
    )
    (net (code "23") (name "Net-(D16-A)") (class "Default")
      (node (ref "D16") (pin "2") (pinfunction "A_2") (pintype "passive"))
      (node (ref "R16") (pin "1") (pinfunction "1_1") (pintype "passive"))
    )
    (net (code "24") (name "Net-(D17-A)") (class "Default")
      (node (ref "D17") (pin "2") (pinfunction "A_2") (pintype "passive"))
      (node (ref "R19") (pin "2") (pinfunction "2_2") (pintype "passive"))
    )
    (net (code "25") (name "Net-(D18-A)") (class "Default")
      (node (ref "D18") (pin "2") (pinfunction "A_2") (pintype "passive"))
      (node (ref "R21") (pin "2") (pinfunction "2_2") (pintype "passive"))
    )
    (net (code "26") (name "Net-(D19-A)") (class "Default")
      (node (ref "D19") (pin "2") (pinfunction "A_2") (pintype "passive"))
      (node (ref "R23") (pin "2") (pinfunction "2_2") (pintype "passive"))
    )
    (net (code "27") (name "Net-(D20-A)") (class "Default")
      (node (ref "D20") (pin "2") (pinfunction "A_2") (pintype "passive"))
      (node (ref "R25") (pin "2") (pinfunction "2_2") (pintype "passive"))
    )
    (net (code "28") (name "Net-(D21-A)") (class "Default")
      (node (ref "D21") (pin "2") (pinfunction "A_2") (pintype "passive"))
      (node (ref "R27") (pin "2") (pinfunction "2_2") (pintype "passive"))
    )
    (net (code "29") (name "Net-(D22-A)") (class "Default")
      (node (ref "D22") (pin "2") (pinfunction "A_2") (pintype "passive"))
      (node (ref "R29") (pin "2") (pinfunction "2_2") (pintype "passive"))
    )
    (net (code "30") (name "Net-(D23-A)") (class "Default")
      (node (ref "D23") (pin "2") (pinfunction "A_2") (pintype "passive"))
      (node (ref "R31") (pin "2") (pinfunction "2_2") (pintype "passive"))
    )
    (net (code "31") (name "Net-(D24-A)") (class "Default")
      (node (ref "D24") (pin "2") (pinfunction "A_2") (pintype "passive"))
      (node (ref "R33") (pin "2") (pinfunction "2_2") (pintype "passive"))
    )
    (net (code "32") (name "Net-(D25-A)") (class "Default")
      (node (ref "D25") (pin "2") (pinfunction "A_2") (pintype "passive"))
      (node (ref "R20") (pin "2") (pinfunction "2_2") (pintype "passive"))
    )
    (net (code "33") (name "Net-(D26-A)") (class "Default")
      (node (ref "D26") (pin "2") (pinfunction "A_2") (pintype "passive"))
      (node (ref "R22") (pin "2") (pinfunction "2_2") (pintype "passive"))
    )
    (net (code "34") (name "Net-(D27-A)") (class "Default")
      (node (ref "D27") (pin "2") (pinfunction "A_2") (pintype "passive"))
      (node (ref "R24") (pin "2") (pinfunction "2_2") (pintype "passive"))
    )
    (net (code "35") (name "Net-(D28-A)") (class "Default")
      (node (ref "D28") (pin "2") (pinfunction "A_2") (pintype "passive"))
      (node (ref "R26") (pin "2") (pinfunction "2_2") (pintype "passive"))
    )
    (net (code "36") (name "Net-(D29-A)") (class "Default")
      (node (ref "D29") (pin "2") (pinfunction "A_2") (pintype "passive"))
      (node (ref "R28") (pin "2") (pinfunction "2_2") (pintype "passive"))
    )
    (net (code "37") (name "Net-(D30-A)") (class "Default")
      (node (ref "D30") (pin "2") (pinfunction "A_2") (pintype "passive"))
      (node (ref "R30") (pin "2") (pinfunction "2_2") (pintype "passive"))
    )
    (net (code "38") (name "Net-(D31-A)") (class "Default")
      (node (ref "D31") (pin "2") (pinfunction "A_2") (pintype "passive"))
      (node (ref "R32") (pin "2") (pinfunction "2_2") (pintype "passive"))
    )
    (net (code "39") (name "Net-(D32-A)") (class "Default")
      (node (ref "D32") (pin "2") (pinfunction "A_2") (pintype "passive"))
      (node (ref "R34") (pin "2") (pinfunction "2_2") (pintype "passive"))
    )
    (net (code "40") (name "Net-(U1-GP0.0)") (class "Default")
      (node (ref "R26") (pin "1") (pinfunction "1_1") (pintype "passive"))
      (node (ref "U1") (pin "21") (pinfunction "GP0.0_21") (pintype "passive"))
    )
    (net (code "41") (name "Net-(U1-GP0.1)") (class "Default")
      (node (ref "R25") (pin "1") (pinfunction "1_1") (pintype "passive"))
      (node (ref "U1") (pin "22") (pinfunction "GP0.1_22") (pintype "passive"))
    )
    (net (code "42") (name "Net-(U1-GP0.2)") (class "Default")
      (node (ref "R24") (pin "1") (pinfunction "1_1") (pintype "passive"))
      (node (ref "U1") (pin "23") (pinfunction "GP0.2_23") (pintype "passive"))
    )
    (net (code "43") (name "Net-(U1-GP0.3)") (class "Default")
      (node (ref "R23") (pin "1") (pinfunction "1_1") (pintype "passive"))
      (node (ref "U1") (pin "24") (pinfunction "GP0.3_24") (pintype "passive"))
    )
    (net (code "44") (name "Net-(U1-GP0.4)") (class "Default")
      (node (ref "R22") (pin "1") (pinfunction "1_1") (pintype "passive"))
      (node (ref "U1") (pin "25") (pinfunction "GP0.4_25") (pintype "passive"))
    )
    (net (code "45") (name "Net-(U1-GP0.5)") (class "Default")
      (node (ref "R21") (pin "1") (pinfunction "1_1") (pintype "passive"))
      (node (ref "U1") (pin "26") (pinfunction "GP0.5_26") (pintype "passive"))
    )
    (net (code "46") (name "Net-(U1-GP0.6)") (class "Default")
      (node (ref "R20") (pin "1") (pinfunction "1_1") (pintype "passive"))
      (node (ref "U1") (pin "27") (pinfunction "GP0.6_27") (pintype "passive"))
    )
    (net (code "47") (name "Net-(U1-GP0.7)") (class "Default")
      (node (ref "R19") (pin "1") (pinfunction "1_1") (pintype "passive"))
      (node (ref "U1") (pin "28") (pinfunction "GP0.7_28") (pintype "passive"))
    )
    (net (code "48") (name "Net-(U1-GP1.0)") (class "Default")
      (node (ref "R1") (pin "2") (pinfunction "2_2") (pintype "passive"))
      (node (ref "U1") (pin "2") (pinfunction "GP1.0_2") (pintype "passive"))
    )
    (net (code "49") (name "Net-(U1-GP1.1)") (class "Default")
      (node (ref "R2") (pin "2") (pinfunction "2_2") (pintype "passive"))
      (node (ref "U1") (pin "3") (pinfunction "GP1.1_3") (pintype "passive"))
    )
    (net (code "50") (name "Net-(U1-GP1.2)") (class "Default")
      (node (ref "R3") (pin "2") (pinfunction "2_2") (pintype "passive"))
      (node (ref "U1") (pin "4") (pinfunction "GP1.2_4") (pintype "passive"))
    )
    (net (code "51") (name "Net-(U1-GP1.3)") (class "Default")
      (node (ref "R4") (pin "2") (pinfunction "2_2") (pintype "passive"))
      (node (ref "U1") (pin "5") (pinfunction "GP1.3_5") (pintype "passive"))
    )
    (net (code "52") (name "Net-(U1-GP1.4)") (class "Default")
      (node (ref "R5") (pin "2") (pinfunction "2_2") (pintype "passive"))
      (node (ref "U1") (pin "7") (pinfunction "GP1.4_7") (pintype "passive"))
    )
    (net (code "53") (name "Net-(U1-GP1.5)") (class "Default")
      (node (ref "R6") (pin "2") (pinfunction "2_2") (pintype "passive"))
      (node (ref "U1") (pin "11") (pinfunction "GP1.5_11") (pintype "passive"))
    )
    (net (code "54") (name "Net-(U1-GP1.6)") (class "Default")
      (node (ref "R7") (pin "2") (pinfunction "2_2") (pintype "passive"))
      (node (ref "U1") (pin "12") (pinfunction "GP1.6_12") (pintype "passive"))
    )
    (net (code "55") (name "Net-(U1-GP1.7)") (class "Default")
      (node (ref "R8") (pin "2") (pinfunction "2_2") (pintype "passive"))
      (node (ref "U1") (pin "13") (pinfunction "GP1.7_13") (pintype "passive"))
    )
    (net (code "56") (name "Net-(U2-A0)") (class "Default")
      (node (ref "R35") (pin "1") (pinfunction "1_1") (pintype "passive"))
      (node (ref "U2") (pin "16") (pinfunction "A0_16") (pintype "passive"))
    )
    (net (code "57") (name "Net-(U2-GP0.0)") (class "Default")
      (node (ref "R34") (pin "1") (pinfunction "1_1") (pintype "passive"))
      (node (ref "U2") (pin "21") (pinfunction "GP0.0_21") (pintype "passive"))
    )
    (net (code "58") (name "Net-(U2-GP0.1)") (class "Default")
      (node (ref "R33") (pin "1") (pinfunction "1_1") (pintype "passive"))
      (node (ref "U2") (pin "22") (pinfunction "GP0.1_22") (pintype "passive"))
    )
    (net (code "59") (name "Net-(U2-GP0.2)") (class "Default")
      (node (ref "R32") (pin "1") (pinfunction "1_1") (pintype "passive"))
      (node (ref "U2") (pin "23") (pinfunction "GP0.2_23") (pintype "passive"))
    )
    (net (code "60") (name "Net-(U2-GP0.3)") (class "Default")
      (node (ref "R31") (pin "1") (pinfunction "1_1") (pintype "passive"))
      (node (ref "U2") (pin "24") (pinfunction "GP0.3_24") (pintype "passive"))
    )
    (net (code "61") (name "Net-(U2-GP0.4)") (class "Default")
      (node (ref "R30") (pin "1") (pinfunction "1_1") (pintype "passive"))
      (node (ref "U2") (pin "25") (pinfunction "GP0.4_25") (pintype "passive"))
    )
    (net (code "62") (name "Net-(U2-GP0.5)") (class "Default")
      (node (ref "R29") (pin "1") (pinfunction "1_1") (pintype "passive"))
      (node (ref "U2") (pin "26") (pinfunction "GP0.5_26") (pintype "passive"))
    )
    (net (code "63") (name "Net-(U2-GP0.6)") (class "Default")
      (node (ref "R28") (pin "1") (pinfunction "1_1") (pintype "passive"))
      (node (ref "U2") (pin "27") (pinfunction "GP0.6_27") (pintype "passive"))
    )
    (net (code "64") (name "Net-(U2-GP0.7)") (class "Default")
      (node (ref "R27") (pin "1") (pinfunction "1_1") (pintype "passive"))
      (node (ref "U2") (pin "28") (pinfunction "GP0.7_28") (pintype "passive"))
    )
    (net (code "65") (name "Net-(U2-GP1.0)") (class "Default")
      (node (ref "R9") (pin "2") (pinfunction "2_2") (pintype "passive"))
      (node (ref "U2") (pin "2") (pinfunction "GP1.0_2") (pintype "passive"))
    )
    (net (code "66") (name "Net-(U2-GP1.1)") (class "Default")
      (node (ref "R10") (pin "2") (pinfunction "2_2") (pintype "passive"))
      (node (ref "U2") (pin "3") (pinfunction "GP1.1_3") (pintype "passive"))
    )
    (net (code "67") (name "Net-(U2-GP1.2)") (class "Default")
      (node (ref "R11") (pin "2") (pinfunction "2_2") (pintype "passive"))
      (node (ref "U2") (pin "4") (pinfunction "GP1.2_4") (pintype "passive"))
    )
    (net (code "68") (name "Net-(U2-GP1.3)") (class "Default")
      (node (ref "R12") (pin "2") (pinfunction "2_2") (pintype "passive"))
      (node (ref "U2") (pin "5") (pinfunction "GP1.3_5") (pintype "passive"))
    )
    (net (code "69") (name "Net-(U2-GP1.4)") (class "Default")
      (node (ref "R13") (pin "2") (pinfunction "2_2") (pintype "passive"))
      (node (ref "U2") (pin "7") (pinfunction "GP1.4_7") (pintype "passive"))
    )
    (net (code "70") (name "Net-(U2-GP1.5)") (class "Default")
      (node (ref "R14") (pin "2") (pinfunction "2_2") (pintype "passive"))
      (node (ref "U2") (pin "11") (pinfunction "GP1.5_11") (pintype "passive"))
    )
    (net (code "71") (name "Net-(U2-GP1.6)") (class "Default")
      (node (ref "R15") (pin "2") (pinfunction "2_2") (pintype "passive"))
      (node (ref "U2") (pin "12") (pinfunction "GP1.6_12") (pintype "passive"))
    )
    (net (code "72") (name "Net-(U2-GP1.7)") (class "Default")
      (node (ref "R16") (pin "2") (pinfunction "2_2") (pintype "passive"))
      (node (ref "U2") (pin "13") (pinfunction "GP1.7_13") (pintype "passive"))
    )
    (net (code "73") (name "unconnected-(U1-TP-Pad10)") (class "Default")
      (node (ref "U1") (pin "10") (pinfunction "TP_10") (pintype "passive"))
    )
    (net (code "74") (name "unconnected-(U1-~{INT}-Pad6)") (class "Default")
      (node (ref "U1") (pin "6") (pinfunction "~{INT}_6") (pintype "passive"))
    )
    (net (code "75") (name "unconnected-(U2-TP-Pad10)") (class "Default")
      (node (ref "U2") (pin "10") (pinfunction "TP_10") (pintype "passive"))
    )
    (net (code "76") (name "unconnected-(U2-~{INT}-Pad6)") (class "Default")
      (node (ref "U2") (pin "6") (pinfunction "~{INT}_6") (pintype "passive"))
    )
  )
)
